# wearable_sch.net
KiCad netlist of a schematic drawn in Altium Designer
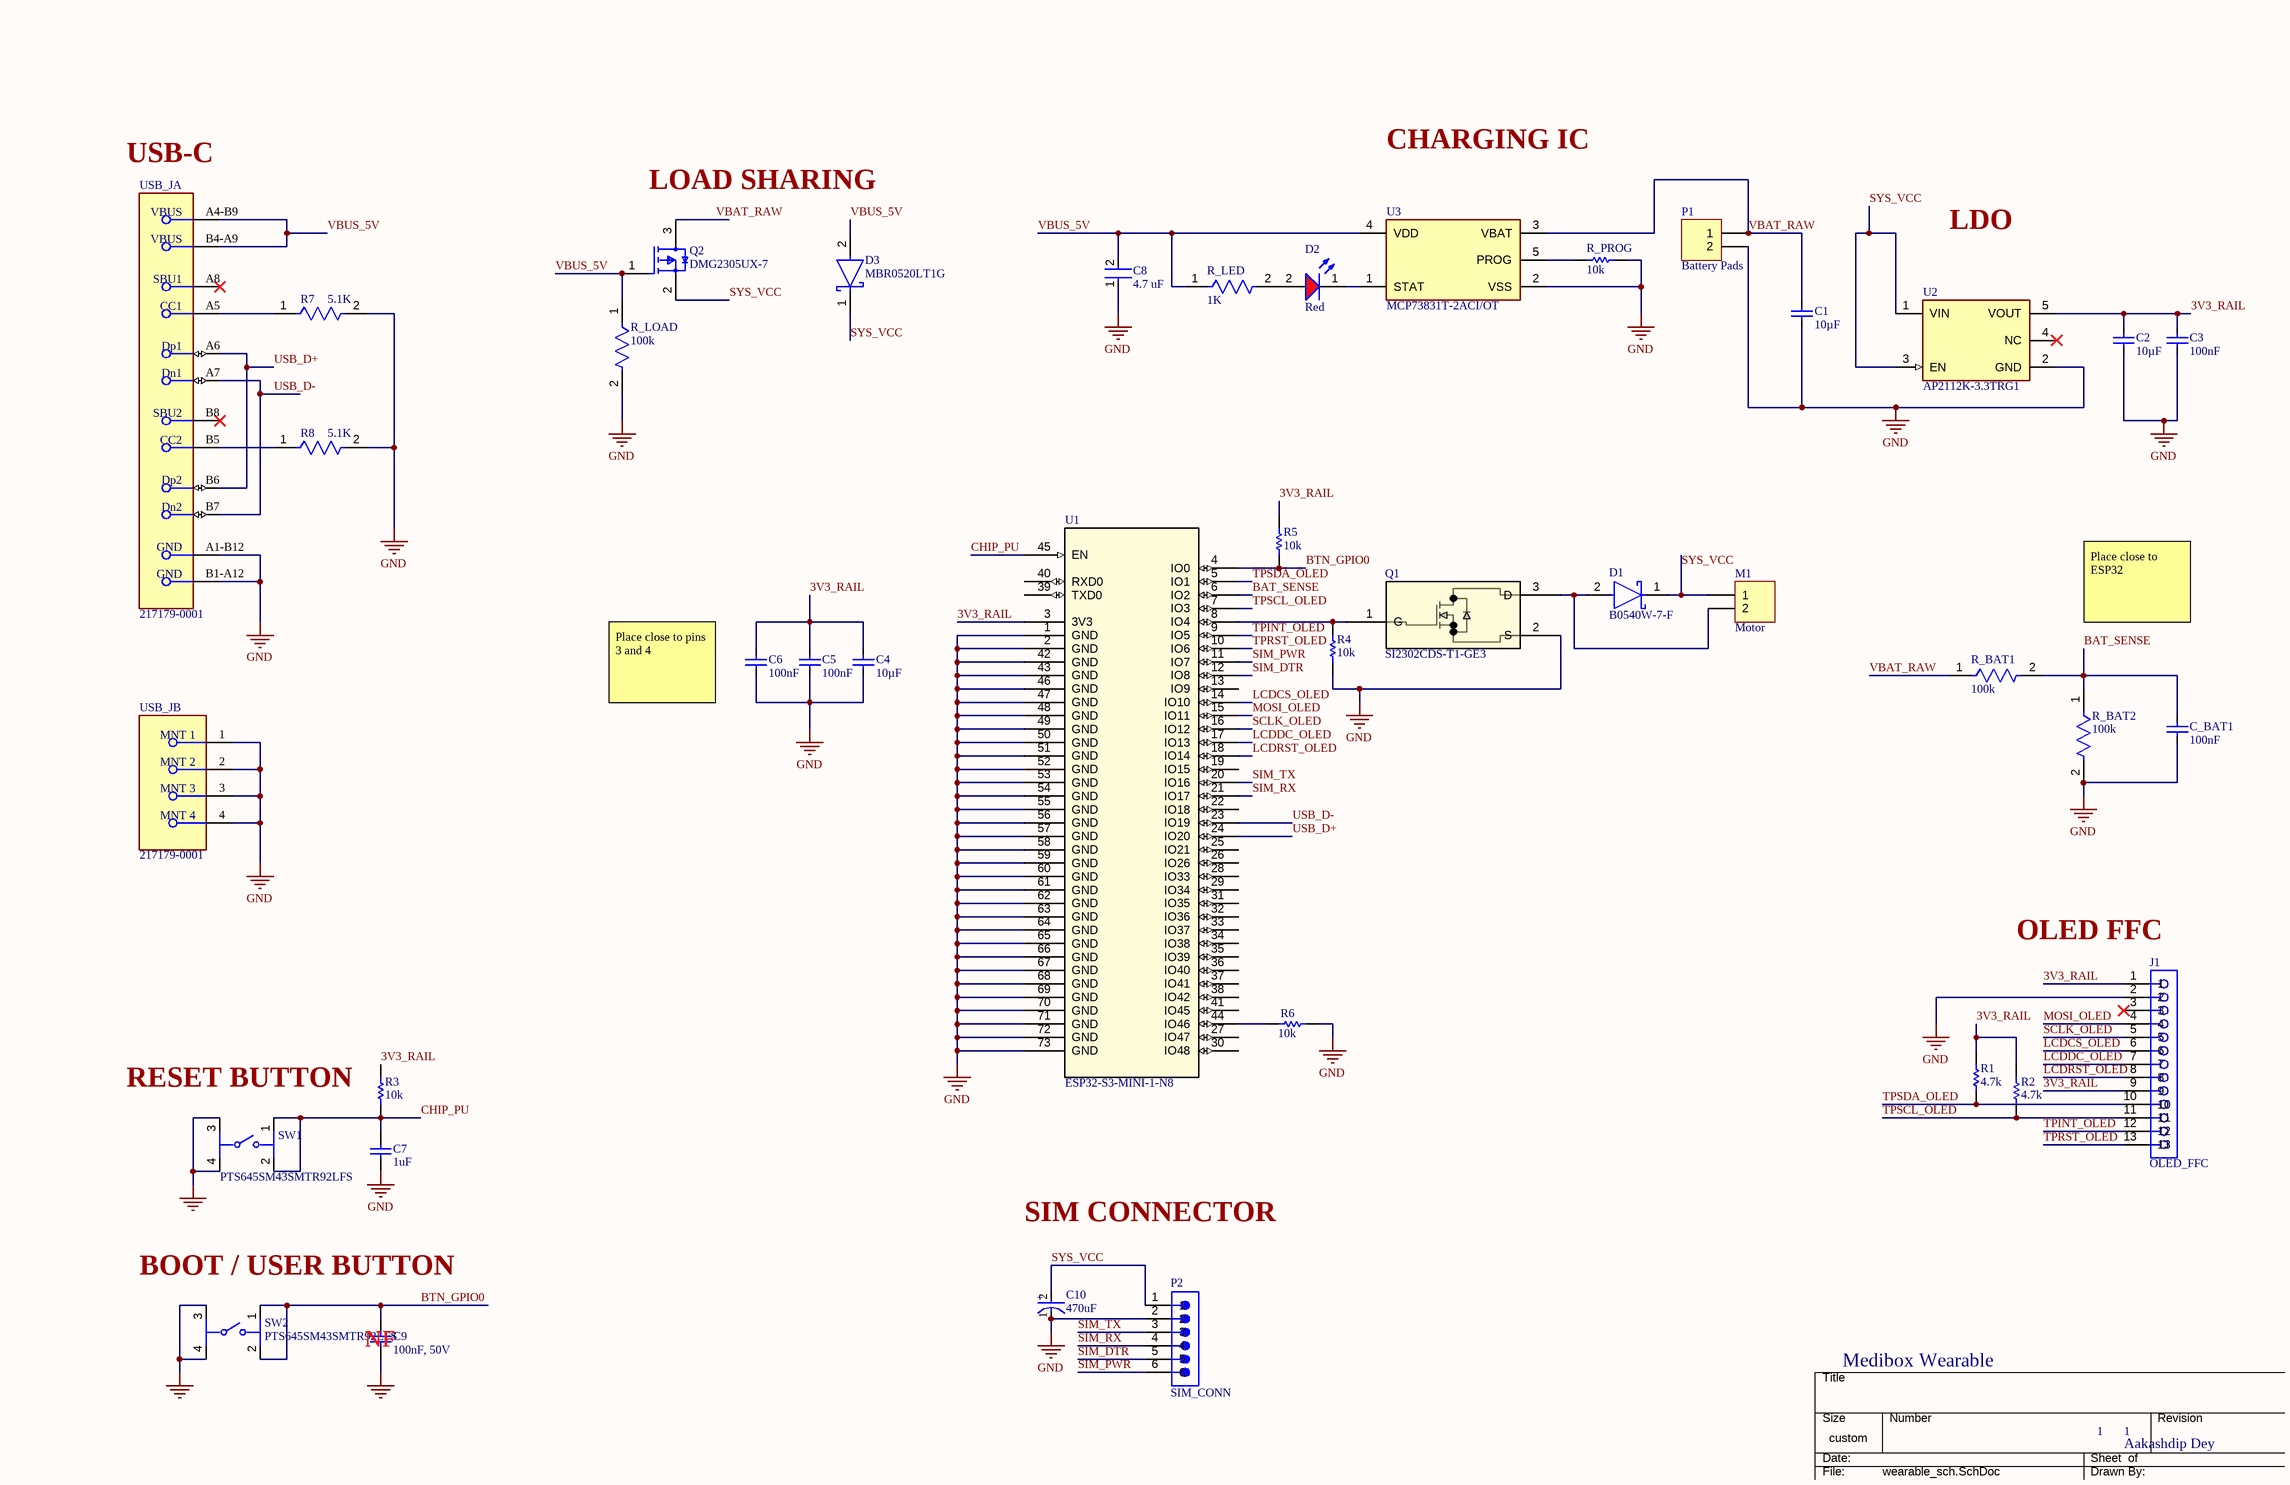
[diagram p0: wearable_sch.SchDoc]

(export (version "E")
  (design (tool "Eeschema 10.0.6"))
  (components
    (comp (ref "C1")
      (value "10µF")
      (footprint "CAPC2013X135X45ML10T25")
      (fields
        (field (name "TOLERANCE") "10%")
        (field (name "MANUFACTURER") "Murata")
        (field (name "MANUFACTURER PART NUMBER") "GRM21BR61E106KA73L")
      )
      (libsource (lib "WCT") (part "CAP_10uF_25V_0805"))
    )
    (comp (ref "C2")
      (value "10µF")
      (footprint "CAPC2013X135X45ML10T25")
      (fields
        (field (name "TOLERANCE") "10%")
        (field (name "MANUFACTURER") "Murata")
        (field (name "MANUFACTURER PART NUMBER") "GRM21BR61E106KA73L")
      )
      (libsource (lib "WCT") (part "CAP_10uF_25V_0805"))
    )
    (comp (ref "C3")
      (value "100nF")
      (footprint "0603C_L")
      (fields
        (field (name "MANUFACTURER") "Yageo")
        (field (name "MANUFACTURER PART NUMBER") "CC0603ZRY5V9BB104")
      )
      (libsource (lib "WCT") (part "Cap100nF_50V_0603"))
    )
    (comp (ref "C4")
      (value "10µF")
      (footprint "CAPC2013X135X45ML10T25")
      (fields
        (field (name "TOLERANCE") "10%")
        (field (name "MANUFACTURER") "Murata")
        (field (name "MANUFACTURER PART NUMBER") "GRM21BR61E106KA73L")
      )
      (libsource (lib "WCT") (part "CAP_10uF_25V_0805"))
    )
    (comp (ref "C5")
      (value "100nF")
      (footprint "0603C_L")
      (fields
        (field (name "MANUFACTURER") "Yageo")
        (field (name "MANUFACTURER PART NUMBER") "CC0603ZRY5V9BB104")
      )
      (libsource (lib "WCT") (part "Cap100nF_50V_0603"))
    )
    (comp (ref "C6")
      (value "100nF")
      (footprint "0603C_L")
      (fields
        (field (name "MANUFACTURER") "Yageo")
        (field (name "MANUFACTURER PART NUMBER") "CC0603ZRY5V9BB104")
      )
      (libsource (lib "WCT") (part "Cap100nF_50V_0603"))
    )
    (comp (ref "C7")
      (value "1uF")
      (footprint "CAPC2013X145X50LL20T25")
      (fields (field (name "MANUFACTURER") "Kemet") (field (name "PART NUMBER") "C0805C105K4PACTU"))
      (libsource (lib "Altium Content Vault") (part "CAP"))
    )
    (comp (ref "C8")
      (value "4.7 uF")
      (footprint "FP-GCM21B-0_15-IPC_A")
      (description "Ceramic Capacitor for Automotive 4.7uF ±20% 16VDC X7R 0805 Embossed T/R")
      (libsource (lib "Altium Content Vault") (part "02cd4be3c70576c341d710602a673aa"))
    )
    (comp (ref "C9")
      (value "100nF, 50V")
      (footprint "0603C_L")
      (description "CAP CER 0.1UF 50V X7R 0402")
      (fields
        (field (name "MANUFACTURER") "Samsung")
        (field (name "MANUFACTURER PART NUMBER") "CL05B104KB54PNC")
      )
      (libsource (lib "Schlib") (part "CL05B104KB54PNC"))
    )
    (comp (ref "C10")
      (value "470uF")
      (footprint "FP-ECAS-D4-MFG")
      (description "ECASD40E477M006KA0 Cap, 470UF, 2.5V, Alu Polymer, 2917 Rohs Compliant: Yes")
      (fields (field (name "TOLERANCE") "20%"))
      (libsource (lib "Altium Content Vault") (part "203bc49f2ac43e59fd269a8c329ed05"))
    )
    (comp (ref "C_BAT1")
      (value "100nF")
      (footprint "0603C_L")
      (fields
        (field (name "MANUFACTURER") "Yageo")
        (field (name "MANUFACTURER PART NUMBER") "CC0603ZRY5V9BB104")
      )
      (libsource (lib "WCT") (part "Cap100nF_50V_0603"))
    )
    (comp (ref "D1")
      (value "B0540W-7-F")
      (footprint "FP-SOD123-MFG")
      (description "DIODE SCHOTTKY 40V 500MA SOD123")
      (fields
        (field (name "MANUFACTURER") "Diodes Inc.")
        (field (name "OCTOPART") "https://octopart.com/b0540w-7-f-diodes+inc.-325656")
      )
      (libsource (lib "Altium Content Vault") (part "1d6ec82d83fb6aee721767c19dac4b9"))
    )
    (comp (ref "D2")
      (value "LED_Red0603")
      (footprint "0603_A")
      (description "Single Color LED, Red, Water Clear, 1.1mm")
      (fields
        (field (name "MANUFACTURER") "Wurth Electronics")
        (field (name "MANUFACTURER PART NUMBER") "150060RS75000")
        (field (name "COLOR") "Red")
      )
      (libsource (lib "WCT") (part "LED_Red0603"))
    )
    (comp (ref "D3")
      (value "MBR0520LT1G")
      (footprint "FP-425-04-IPC_C")
      (description "DIODE SCHOTTKY 20V 500MA SOD123")
      (libsource (lib "Altium Content Vault") (part "1d6ec82d83fb6aee721767c19dac4b9"))
    )
    (comp (ref "J1")
      (value "OLED_FFC")
      (footprint "MOLX-52806-1310")
      (fields (field (name "PARTNUMBER") "52806-1310") (field (name "MANUFACTURER") "Molex"))
      (libsource (lib "Altium Content Vault") (part "MOLX-52806-1310"))
    )
    (comp (ref "M1")
      (value "Motor")
      (footprint "HDR1X2")
      (description "Header, 2-Pin")
      (fields (field (name "PUBLISHER") "Altium Limited"))
      (libsource (lib "Miscellaneous Connectors") (part "Header 2"))
    )
    (comp (ref "P1")
      (value "Battery Pads")
      (footprint "HDR1X2")
      (description "Header, 2-Pin")
      (fields (field (name "PUBLISHER") "Altium Limited"))
      (libsource (lib "") (part "Header 2_1"))
    )
    (comp (ref "P2")
      (value "SIM_CONN")
      (footprint "SMTC-TSW-106-23-X-S")
      (description "0.025\" SQ Post Header, Through-hole, Vertical, -55 to 125 degC, 2.54 mm Pitch, 6-Pin, Male, RoHS")
      (fields (field (name "MANUFACTURER") "Samtec") (field (name "PARTNUMBER") "TSW-106-23-L-S"))
      (libsource (lib "Altium Content Vault") (part "SMTC-TSW-106-X-X-S-X"))
    )
    (comp (ref "Q1")
      (value "SI2302CDS-T1-GE3")
      (footprint "TO-236_VIS-L")
      (description "N-CHANNEL 20-V (D-S) MOSFET")
      (fields (field (name "COPYRIGHT") "Copyright (C) 2026 Ultra Librarian. All rights reserved."))
      (libsource (lib "wearable") (part "SI2302CDS-T1-GE3"))
    )
    (comp (ref "Q2")
      (value "DMG2305UX-7")
      (footprint "FP-SOT23-IPC_B")
      (description "MOSFET P-CH 20V 4.2A SOT23")
      (libsource (lib "Altium Content Vault") (part "87831b450059b469d4a68f5364f4496"))
    )
    (comp (ref "R1")
      (value "4.7k")
      (footprint "0603_L")
      (description "Res4K7_0603")
      (fields
        (field (name "MANUFACTURER") "Yageo")
        (field (name "TOLERANCE") "0.5%")
        (field (name "SOURCE") "WCT.SchLib")
      )
      (libsource (lib "WCT") (part "Res4K7_0603"))
    )
    (comp (ref "R2")
      (value "4.7k")
      (footprint "0603_L")
      (description "Res4K7_0603")
      (fields
        (field (name "MANUFACTURER") "Yageo")
        (field (name "TOLERANCE") "0.5%")
        (field (name "SOURCE") "WCT.SchLib")
      )
      (libsource (lib "WCT") (part "Res4K7_0603"))
    )
    (comp (ref "R3")
      (value "10k")
      (footprint "0603_L")
      (description "Res10K_0603")
      (fields
        (field (name "MANUFACTURER") "Panasonic Electronic Components")
        (field (name "MANUFACTURER PART NUMBER") "ERJ-3GEYJ102V")
        (field (name "SOURCE") "WCT.SchLib")
      )
      (libsource (lib "WCT") (part "Res10K_0603"))
    )
    (comp (ref "R4")
      (value "10k")
      (footprint "0603_L")
      (description "Res10K_0603")
      (fields
        (field (name "MANUFACTURER") "Panasonic Electronic Components")
        (field (name "MANUFACTURER PART NUMBER") "ERJ-3GEYJ102V")
        (field (name "SOURCE") "WCT.SchLib")
      )
      (libsource (lib "WCT") (part "Res10K_0603"))
    )
    (comp (ref "R5")
      (value "10k")
      (footprint "0603_L")
      (description "Res10K_0603")
      (fields
        (field (name "MANUFACTURER") "Panasonic Electronic Components")
        (field (name "MANUFACTURER PART NUMBER") "ERJ-3GEYJ102V")
        (field (name "SOURCE") "WCT.SchLib")
      )
      (libsource (lib "WCT") (part "Res10K_0603"))
    )
    (comp (ref "R6")
      (value "10k")
      (footprint "0603_L")
      (description "Res10K_0603")
      (fields
        (field (name "MANUFACTURER") "Panasonic Electronic Components")
        (field (name "MANUFACTURER PART NUMBER") "ERJ-3GEYJ102V")
        (field (name "SOURCE") "WCT.SchLib")
      )
      (libsource (lib "WCT") (part "Res10K_0603"))
    )
    (comp (ref "R7")
      (value "5.1K")
      (footprint "FP-CRCW0402-e3-IPC_A")
      (description "RES Thick Film, 5.1kΩ, 5%, 0.063W, 200ppm/°C, 0402")
      (fields (field (name "TOLERANCE") "5%"))
      (libsource (lib "Altium Content Vault") (part "1029c3af85768c4190bb7ad29bc67b5"))
    )
    (comp (ref "R8")
      (value "5.1K")
      (footprint "FP-CRCW0402-e3-IPC_A")
      (description "RES Thick Film, 5.1kΩ, 5%, 0.063W, 200ppm/°C, 0402")
      (fields (field (name "TOLERANCE") "5%"))
      (libsource (lib "Altium Content Vault") (part "1029c3af85768c4190bb7ad29bc67b5"))
    )
    (comp (ref "R_BAT1")
      (value "100k")
      (footprint "FP-MCS0402-MFG")
      (description "RES SMD 1.2K OHM 1% 1/10W 0402")
      (fields (field (name "TOLERANCE") "0.1%"))
      (libsource (lib "Altium Content Vault") (part "1029c3af85768c4190bb7ad29bc67b5"))
    )
    (comp (ref "R_BAT2")
      (value "100k")
      (footprint "FP-MCS0402-MFG")
      (description "RES SMD 1.2K OHM 1% 1/10W 0402")
      (fields (field (name "TOLERANCE") "0.1%"))
      (libsource (lib "Altium Content Vault") (part "1029c3af85768c4190bb7ad29bc67b5"))
    )
    (comp (ref "R_LED")
      (value "1K")
      (footprint "FP-AC0402-IPC_C")
      (description "RES 1kΩ ±1% 0.063W 0402")
      (libsource (lib "Altium Content Vault") (part "1029c3af85768c4190bb7ad29bc67b5"))
    )
    (comp (ref "R_LOAD")
      (value "100k")
      (footprint "FP-MCS0402-MFG")
      (description "RES SMD 1.2K OHM 1% 1/10W 0402")
      (fields (field (name "TOLERANCE") "0.1%"))
      (libsource (lib "Altium Content Vault") (part "1029c3af85768c4190bb7ad29bc67b5"))
    )
    (comp (ref "R_PROG")
      (value "10k")
      (footprint "0603_L")
      (description "Res10K_0603")
      (fields
        (field (name "MANUFACTURER") "Panasonic Electronic Components")
        (field (name "MANUFACTURER PART NUMBER") "ERJ-3GEYJ102V")
        (field (name "SOURCE") "WCT.SchLib")
      )
      (libsource (lib "WCT") (part "Res10K_0603"))
    )
    (comp (ref "SW1")
      (value "PTS645SM43SMTR92LFS")
      (footprint "FP-PTS645SM43SMTR92LFS-MFG")
      (description "SWITCH TACTILE SPST-NO 0.05A 12V")
      (libsource (lib "wearable") (part "CMP-2000-05160-2"))
    )
    (comp (ref "SW2")
      (value "PTS645SM43SMTR92LFS")
      (footprint "FP-PTS645SM43SMTR92LFS-MFG")
      (description "SWITCH TACTILE SPST-NO 0.05A 12V")
      (libsource (lib "wearable") (part "CMP-2000-05160-2"))
    )
    (comp (ref "U1")
      (value "ESP32-S3-MINI-1-N8")
      (footprint "ESP32-S3-MINI-1_EXP")
      (description "SMD module, ESP32-S3FN8, 8 MB SPI flash, PCB antenna")
      (fields (field (name "MANUFACTURER") "Espressif Systems") (field (name "LCSC PART NO.") "C2913206"))
      (libsource (lib "wearable") (part "ESP32-S3"))
    )
    (comp (ref "U2")
      (value "AP2112K-3.3TRG1")
      (footprint "FP-SOT25-IPC_A")
      (description "IC REG LINEAR 3.3V 600MA SOT25")
      (libsource (lib "Altium Content Vault") (part "c8ab751aee5229183125ab046a11caa"))
    )
    (comp (ref "U3")
      (value "MCP73831T-2ACI/OT")
      (footprint "FP-C04-091-OT-IPC_B")
      (description "IC CONTROLLR LI-ION 4.2V SOT23-5")
      (libsource (lib "Altium Content Vault") (part "61f5a3bb3429d9e0caadea342aa3b19"))
    )
    (comp (ref "USB_J")
      (value "217179-0001")
      (footprint "FP-2171790001-MFG")
      (description "CONN RCP USB2.0 TYP C 24P SMD RA")
      (libsource (lib "Altium Content Vault") (part "8b86497a633d14b3f74642136fc0ce6"))
    )
  )
  (nets
    (net (code "1") (name "/3V3_RAIL") (class "Default")
      (node (ref "C2") (pin "2") (pinfunction "2_2") (pintype "passive"))
      (node (ref "C3") (pin "2") (pinfunction "2_2") (pintype "passive"))
      (node (ref "C4") (pin "2") (pinfunction "2_2") (pintype "passive"))
      (node (ref "C5") (pin "2") (pinfunction "2_2") (pintype "passive"))
      (node (ref "C6") (pin "2") (pinfunction "2_2") (pintype "passive"))
      (node (ref "J1") (pin "1") (pinfunction "1_1") (pintype "passive"))
      (node (ref "J1") (pin "9") (pinfunction "9_9") (pintype "passive"))
      (node (ref "R1") (pin "2") (pinfunction "2_2") (pintype "passive"))
      (node (ref "R2") (pin "2") (pinfunction "2_2") (pintype "passive"))
      (node (ref "R3") (pin "1") (pinfunction "1_1") (pintype "passive"))
      (node (ref "R5") (pin "2") (pinfunction "2_2") (pintype "passive"))
      (node (ref "U1") (pin "3") (pinfunction "3V3_3") (pintype "power_in"))
      (node (ref "U2") (pin "5") (pinfunction "VOUT_5") (pintype "power_in"))
    )
    (net (code "2") (name "/BAT_SENSE") (class "Default")
      (node (ref "C_BAT1") (pin "2") (pinfunction "2_2") (pintype "passive"))
      (node (ref "R_BAT1") (pin "2") (pinfunction "2_2") (pintype "passive"))
      (node (ref "R_BAT2") (pin "1") (pinfunction "1_1") (pintype "passive"))
      (node (ref "U1") (pin "6") (pinfunction "IO2_6") (pintype "bidirectional"))
    )
    (net (code "3") (name "/BTN_GPIO0") (class "Default")
      (node (ref "C9") (pin "2") (pinfunction "2_2") (pintype "passive"))
      (node (ref "R5") (pin "1") (pinfunction "1_1") (pintype "passive"))
      (node (ref "SW2") (pin "1") (pinfunction "1_1") (pintype "passive"))
      (node (ref "SW2") (pin "2") (pinfunction "2_2") (pintype "passive"))
      (node (ref "U1") (pin "4") (pinfunction "IO0_4") (pintype "bidirectional"))
    )
    (net (code "4") (name "/CHIP_PU") (class "Default")
      (node (ref "C7") (pin "2") (pinfunction "2_2") (pintype "passive"))
      (node (ref "R3") (pin "2") (pinfunction "2_2") (pintype "passive"))
      (node (ref "SW1") (pin "1") (pinfunction "1_1") (pintype "passive"))
      (node (ref "SW1") (pin "2") (pinfunction "2_2") (pintype "passive"))
      (node (ref "U1") (pin "45") (pinfunction "EN_45") (pintype "input"))
    )
    (net (code "5") (name "/LCDCS_OLED") (class "Default")
      (node (ref "J1") (pin "6") (pinfunction "6_6") (pintype "passive"))
      (node (ref "U1") (pin "14") (pinfunction "IO10_14") (pintype "bidirectional"))
    )
    (net (code "6") (name "/LCDDC_OLED") (class "Default")
      (node (ref "J1") (pin "7") (pinfunction "7_7") (pintype "passive"))
      (node (ref "U1") (pin "17") (pinfunction "IO13_17") (pintype "bidirectional"))
    )
    (net (code "7") (name "/LCDRST_OLED") (class "Default")
      (node (ref "J1") (pin "8") (pinfunction "8_8") (pintype "passive"))
      (node (ref "U1") (pin "18") (pinfunction "IO14_18") (pintype "bidirectional"))
    )
    (net (code "8") (name "/MOSI_OLED") (class "Default")
      (node (ref "J1") (pin "4") (pinfunction "4_4") (pintype "passive"))
      (node (ref "U1") (pin "15") (pinfunction "IO11_15") (pintype "bidirectional"))
    )
    (net (code "9") (name "/SCLK_OLED") (class "Default")
      (node (ref "J1") (pin "5") (pinfunction "5_5") (pintype "passive"))
      (node (ref "U1") (pin "16") (pinfunction "IO12_16") (pintype "bidirectional"))
    )
    (net (code "10") (name "/SIM_DTR") (class "Default")
      (node (ref "P2") (pin "5") (pinfunction "5_5") (pintype "passive"))
      (node (ref "U1") (pin "12") (pinfunction "IO8_12") (pintype "bidirectional"))
    )
    (net (code "11") (name "/SIM_PWR") (class "Default")
      (node (ref "P2") (pin "6") (pinfunction "6_6") (pintype "passive"))
      (node (ref "U1") (pin "11") (pinfunction "IO7_11") (pintype "bidirectional"))
    )
    (net (code "12") (name "/SIM_RX") (class "Default")
      (node (ref "P2") (pin "4") (pinfunction "4_4") (pintype "passive"))
      (node (ref "U1") (pin "21") (pinfunction "IO17_21") (pintype "bidirectional"))
    )
    (net (code "13") (name "/SIM_TX") (class "Default")
      (node (ref "P2") (pin "3") (pinfunction "3_3") (pintype "passive"))
      (node (ref "U1") (pin "20") (pinfunction "IO16_20") (pintype "bidirectional"))
    )
    (net (code "14") (name "/SYS_VCC") (class "Default")
      (node (ref "C10") (pin "2") (pinfunction "A_2") (pintype "passive"))
      (node (ref "D1") (pin "1") (pinfunction "C_1") (pintype "passive"))
      (node (ref "D3") (pin "1") (pinfunction "C_1") (pintype "passive"))
      (node (ref "M1") (pin "1") (pinfunction "1_1") (pintype "passive"))
      (node (ref "P2") (pin "1") (pinfunction "1_1") (pintype "passive"))
      (node (ref "Q2") (pin "2") (pinfunction "SOURCE_2") (pintype "passive"))
      (node (ref "U2") (pin "1") (pinfunction "VIN_1") (pintype "power_in"))
      (node (ref "U2") (pin "3") (pinfunction "EN_3") (pintype "input"))
    )
    (net (code "15") (name "/TPINT_OLED") (class "Default")
      (node (ref "J1") (pin "12") (pinfunction "12_12") (pintype "passive"))
      (node (ref "U1") (pin "9") (pinfunction "IO5_9") (pintype "bidirectional"))
    )
    (net (code "16") (name "/TPRST_OLED") (class "Default")
      (node (ref "J1") (pin "13") (pinfunction "13_13") (pintype "passive"))
      (node (ref "U1") (pin "10") (pinfunction "IO6_10") (pintype "bidirectional"))
    )
    (net (code "17") (name "/TPSCL_OLED") (class "Default")
      (node (ref "J1") (pin "11") (pinfunction "11_11") (pintype "passive"))
      (node (ref "R2") (pin "1") (pinfunction "1_1") (pintype "passive"))
      (node (ref "U1") (pin "7") (pinfunction "IO3_7") (pintype "bidirectional"))
    )
    (net (code "18") (name "/TPSDA_OLED") (class "Default")
      (node (ref "J1") (pin "10") (pinfunction "10_10") (pintype "passive"))
      (node (ref "R1") (pin "1") (pinfunction "1_1") (pintype "passive"))
      (node (ref "U1") (pin "5") (pinfunction "IO1_5") (pintype "bidirectional"))
    )
    (net (code "19") (name "/USB_D+") (class "Default")
      (node (ref "U1") (pin "24") (pinfunction "IO20_24") (pintype "bidirectional"))
      (node (ref "USB_J") (pin "A6") (pinfunction "Dp1_A6") (pintype "bidirectional"))
      (node (ref "USB_J") (pin "B6") (pinfunction "Dp2_B6") (pintype "bidirectional"))
    )
    (net (code "20") (name "/USB_D-") (class "Default")
      (node (ref "U1") (pin "23") (pinfunction "IO19_23") (pintype "bidirectional"))
      (node (ref "USB_J") (pin "A7") (pinfunction "Dn1_A7") (pintype "bidirectional"))
      (node (ref "USB_J") (pin "B7") (pinfunction "Dn2_B7") (pintype "bidirectional"))
    )
    (net (code "21") (name "/VBAT_RAW") (class "Default")
      (node (ref "C1") (pin "1") (pinfunction "1_1") (pintype "passive"))
      (node (ref "P1") (pin "1") (pinfunction "1_1") (pintype "passive"))
      (node (ref "Q2") (pin "3") (pinfunction "DRAIN_3") (pintype "passive"))
      (node (ref "R_BAT1") (pin "1") (pinfunction "1_1") (pintype "passive"))
      (node (ref "U3") (pin "3") (pinfunction "VBAT_3") (pintype "power_in"))
    )
    (net (code "22") (name "/VBUS_5V") (class "Default")
      (node (ref "C8") (pin "2") (pinfunction "2_2") (pintype "passive"))
      (node (ref "D3") (pin "2") (pinfunction "A_2") (pintype "passive"))
      (node (ref "Q2") (pin "1") (pinfunction "GATE_1") (pintype "passive"))
      (node (ref "R_LED") (pin "1") (pinfunction "1_1") (pintype "passive"))
      (node (ref "R_LOAD") (pin "1") (pinfunction "1_1") (pintype "passive"))
      (node (ref "U3") (pin "4") (pinfunction "VDD_4") (pintype "power_in"))
      (node (ref "USB_J") (pin "A4-B9") (pinfunction "VBUS_A4-B9") (pintype "power_in"))
      (node (ref "USB_J") (pin "B4-A9") (pinfunction "VBUS_B4-A9") (pintype "power_in"))
    )
    (net (code "23") (name "GND") (class "Default")
      (node (ref "C1") (pin "2") (pinfunction "2_2") (pintype "passive"))
      (node (ref "C10") (pin "1") (pinfunction "C_1") (pintype "passive"))
      (node (ref "C2") (pin "1") (pinfunction "1_1") (pintype "passive"))
      (node (ref "C3") (pin "1") (pinfunction "1_1") (pintype "passive"))
      (node (ref "C4") (pin "1") (pinfunction "1_1") (pintype "passive"))
      (node (ref "C5") (pin "1") (pinfunction "1_1") (pintype "passive"))
      (node (ref "C6") (pin "1") (pinfunction "1_1") (pintype "passive"))
      (node (ref "C7") (pin "1") (pinfunction "1_1") (pintype "passive"))
      (node (ref "C8") (pin "1") (pinfunction "1_1") (pintype "passive"))
      (node (ref "C9") (pin "1") (pinfunction "1_1") (pintype "passive"))
      (node (ref "C_BAT1") (pin "1") (pinfunction "1_1") (pintype "passive"))
      (node (ref "J1") (pin "2") (pinfunction "2_2") (pintype "passive"))
      (node (ref "P1") (pin "2") (pinfunction "2_2") (pintype "passive"))
      (node (ref "P2") (pin "2") (pinfunction "2_2") (pintype "passive"))
      (node (ref "Q1") (pin "2") (pinfunction "S_2") (pintype "passive"))
      (node (ref "R4") (pin "1") (pinfunction "1_1") (pintype "passive"))
      (node (ref "R6") (pin "2") (pinfunction "2_2") (pintype "passive"))
      (node (ref "R7") (pin "2") (pinfunction "2_2") (pintype "passive"))
      (node (ref "R8") (pin "2") (pinfunction "2_2") (pintype "passive"))
      (node (ref "R_BAT2") (pin "2") (pinfunction "2_2") (pintype "passive"))
      (node (ref "R_LOAD") (pin "2") (pinfunction "2_2") (pintype "passive"))
      (node (ref "R_PROG") (pin "2") (pinfunction "2_2") (pintype "passive"))
      (node (ref "SW1") (pin "3") (pinfunction "3_3") (pintype "passive"))
      (node (ref "SW1") (pin "4") (pinfunction "4_4") (pintype "passive"))
      (node (ref "SW2") (pin "3") (pinfunction "3_3") (pintype "passive"))
      (node (ref "SW2") (pin "4") (pinfunction "4_4") (pintype "passive"))
      (node (ref "U1") (pin "1") (pinfunction "GND_1") (pintype "power_in"))
      (node (ref "U1") (pin "2") (pinfunction "GND_2") (pintype "power_in"))
      (node (ref "U1") (pin "42") (pinfunction "GND_42") (pintype "power_in"))
      (node (ref "U1") (pin "43") (pinfunction "GND_43") (pintype "power_in"))
      (node (ref "U1") (pin "46") (pinfunction "GND_46") (pintype "power_in"))
      (node (ref "U1") (pin "47") (pinfunction "GND_47") (pintype "power_in"))
      (node (ref "U1") (pin "48") (pinfunction "GND_48") (pintype "power_in"))
      (node (ref "U1") (pin "49") (pinfunction "GND_49") (pintype "power_in"))
      (node (ref "U1") (pin "50") (pinfunction "GND_50") (pintype "power_in"))
      (node (ref "U1") (pin "51") (pinfunction "GND_51") (pintype "power_in"))
      (node (ref "U1") (pin "52") (pinfunction "GND_52") (pintype "power_in"))
      (node (ref "U1") (pin "53") (pinfunction "GND_53") (pintype "power_in"))
      (node (ref "U1") (pin "54") (pinfunction "GND_54") (pintype "power_in"))
      (node (ref "U1") (pin "55") (pinfunction "GND_55") (pintype "power_in"))
      (node (ref "U1") (pin "56") (pinfunction "GND_56") (pintype "power_in"))
      (node (ref "U1") (pin "57") (pinfunction "GND_57") (pintype "power_in"))
      (node (ref "U1") (pin "58") (pinfunction "GND_58") (pintype "power_in"))
      (node (ref "U1") (pin "59") (pinfunction "GND_59") (pintype "power_in"))
      (node (ref "U1") (pin "60") (pinfunction "GND_60") (pintype "power_in"))
      (node (ref "U1") (pin "61") (pinfunction "GND_61") (pintype "power_in"))
      (node (ref "U1") (pin "62") (pinfunction "GND_62") (pintype "power_in"))
      (node (ref "U1") (pin "63") (pinfunction "GND_63") (pintype "power_in"))
      (node (ref "U1") (pin "64") (pinfunction "GND_64") (pintype "power_in"))
      (node (ref "U1") (pin "65") (pinfunction "GND_65") (pintype "power_in"))
      (node (ref "U1") (pin "66") (pinfunction "GND_66") (pintype "power_in"))
      (node (ref "U1") (pin "67") (pinfunction "GND_67") (pintype "power_in"))
      (node (ref "U1") (pin "68") (pinfunction "GND_68") (pintype "power_in"))
      (node (ref "U1") (pin "69") (pinfunction "GND_69") (pintype "power_in"))
      (node (ref "U1") (pin "70") (pinfunction "GND_70") (pintype "power_in"))
      (node (ref "U1") (pin "71") (pinfunction "GND_71") (pintype "power_in"))
      (node (ref "U1") (pin "72") (pinfunction "GND_72") (pintype "power_in"))
      (node (ref "U1") (pin "73") (pinfunction "GND_73") (pintype "power_in"))
      (node (ref "U2") (pin "2") (pinfunction "GND_2") (pintype "power_in"))
      (node (ref "U3") (pin "2") (pinfunction "VSS_2") (pintype "power_in"))
      (node (ref "USB_J") (pin "1") (pinfunction "MNT_1_1") (pintype "passive"))
      (node (ref "USB_J") (pin "2") (pinfunction "MNT_2_2") (pintype "passive"))
      (node (ref "USB_J") (pin "3") (pinfunction "MNT_3_3") (pintype "power_in"))
      (node (ref "USB_J") (pin "4") (pinfunction "MNT_4_4") (pintype "power_in"))
      (node (ref "USB_J") (pin "A1-B12") (pinfunction "GND_A1-B12") (pintype "power_in"))
      (node (ref "USB_J") (pin "B1-A12") (pinfunction "GND_B1-A12") (pintype "power_in"))
    )
    (net (code "24") (name "Net-(D1-A)") (class "Default")
      (node (ref "D1") (pin "2") (pinfunction "A_2") (pintype "passive"))
      (node (ref "M1") (pin "2") (pinfunction "2_2") (pintype "passive"))
      (node (ref "Q1") (pin "3") (pinfunction "D_3") (pintype "passive"))
    )
    (net (code "25") (name "Net-(D2-A)") (class "Default")
      (node (ref "D2") (pin "2") (pinfunction "A_2") (pintype "passive"))
      (node (ref "R_LED") (pin "2") (pinfunction "2_2") (pintype "passive"))
    )
    (net (code "26") (name "Net-(D2-K)") (class "Default")
      (node (ref "D2") (pin "1") (pinfunction "K_1") (pintype "passive"))
      (node (ref "U3") (pin "1") (pinfunction "STAT_1") (pintype "passive"))
    )
    (net (code "27") (name "Net-(Q1-G)") (class "Default")
      (node (ref "Q1") (pin "1") (pinfunction "G_1") (pintype "passive"))
      (node (ref "R4") (pin "2") (pinfunction "2_2") (pintype "passive"))
      (node (ref "U1") (pin "8") (pinfunction "IO4_8") (pintype "bidirectional"))
    )
    (net (code "28") (name "Net-(U1-IO46)") (class "Default")
      (node (ref "R6") (pin "1") (pinfunction "1_1") (pintype "passive"))
      (node (ref "U1") (pin "44") (pinfunction "IO46_44") (pintype "bidirectional"))
    )
    (net (code "29") (name "Net-(U3-PROG)") (class "Default")
      (node (ref "R_PROG") (pin "1") (pinfunction "1_1") (pintype "passive"))
      (node (ref "U3") (pin "5") (pinfunction "PROG_5") (pintype "passive"))
    )
    (net (code "30") (name "Net-(USB_JA-CC1)") (class "Default")
      (node (ref "R7") (pin "1") (pinfunction "1_1") (pintype "passive"))
      (node (ref "USB_J") (pin "A5") (pinfunction "CC1_A5") (pintype "passive"))
    )
    (net (code "31") (name "Net-(USB_JA-CC2)") (class "Default")
      (node (ref "R8") (pin "1") (pinfunction "1_1") (pintype "passive"))
      (node (ref "USB_J") (pin "B5") (pinfunction "CC2_B5") (pintype "passive"))
    )
    (net (code "32") (name "unconnected-(J1-Pad3)") (class "Default")
      (node (ref "J1") (pin "3") (pinfunction "3_3") (pintype "passive+no_connect"))
    )
    (net (code "33") (name "unconnected-(U1-IO9-Pad13)") (class "Default")
      (node (ref "U1") (pin "13") (pinfunction "IO9_13") (pintype "bidirectional"))
    )
    (net (code "34") (name "unconnected-(U1-IO15-Pad19)") (class "Default")
      (node (ref "U1") (pin "19") (pinfunction "IO15_19") (pintype "bidirectional"))
    )
    (net (code "35") (name "unconnected-(U1-IO18-Pad22)") (class "Default")
      (node (ref "U1") (pin "22") (pinfunction "IO18_22") (pintype "bidirectional"))
    )
    (net (code "36") (name "unconnected-(U1-IO21-Pad25)") (class "Default")
      (node (ref "U1") (pin "25") (pinfunction "IO21_25") (pintype "bidirectional"))
    )
    (net (code "37") (name "unconnected-(U1-IO26-Pad26)") (class "Default")
      (node (ref "U1") (pin "26") (pinfunction "IO26_26") (pintype "bidirectional"))
    )
    (net (code "38") (name "unconnected-(U1-IO33-Pad28)") (class "Default")
      (node (ref "U1") (pin "28") (pinfunction "IO33_28") (pintype "bidirectional"))
    )
    (net (code "39") (name "unconnected-(U1-IO34-Pad29)") (class "Default")
      (node (ref "U1") (pin "29") (pinfunction "IO34_29") (pintype "bidirectional"))
    )
    (net (code "40") (name "unconnected-(U1-IO35-Pad31)") (class "Default")
      (node (ref "U1") (pin "31") (pinfunction "IO35_31") (pintype "bidirectional"))
    )
    (net (code "41") (name "unconnected-(U1-IO36-Pad32)") (class "Default")
      (node (ref "U1") (pin "32") (pinfunction "IO36_32") (pintype "bidirectional"))
    )
    (net (code "42") (name "unconnected-(U1-IO37-Pad33)") (class "Default")
      (node (ref "U1") (pin "33") (pinfunction "IO37_33") (pintype "bidirectional"))
    )
    (net (code "43") (name "unconnected-(U1-IO38-Pad34)") (class "Default")
      (node (ref "U1") (pin "34") (pinfunction "IO38_34") (pintype "bidirectional"))
    )
    (net (code "44") (name "unconnected-(U1-IO39-Pad35)") (class "Default")
      (node (ref "U1") (pin "35") (pinfunction "IO39_35") (pintype "bidirectional"))
    )
    (net (code "45") (name "unconnected-(U1-IO40-Pad36)") (class "Default")
      (node (ref "U1") (pin "36") (pinfunction "IO40_36") (pintype "bidirectional"))
    )
    (net (code "46") (name "unconnected-(U1-IO41-Pad37)") (class "Default")
      (node (ref "U1") (pin "37") (pinfunction "IO41_37") (pintype "bidirectional"))
    )
    (net (code "47") (name "unconnected-(U1-IO42-Pad38)") (class "Default")
      (node (ref "U1") (pin "38") (pinfunction "IO42_38") (pintype "bidirectional"))
    )
    (net (code "48") (name "unconnected-(U1-IO45-Pad41)") (class "Default")
      (node (ref "U1") (pin "41") (pinfunction "IO45_41") (pintype "bidirectional"))
    )
    (net (code "49") (name "unconnected-(U1-IO47-Pad27)") (class "Default")
      (node (ref "U1") (pin "27") (pinfunction "IO47_27") (pintype "bidirectional"))
    )
    (net (code "50") (name "unconnected-(U1-IO48-Pad30)") (class "Default")
      (node (ref "U1") (pin "30") (pinfunction "IO48_30") (pintype "bidirectional"))
    )
    (net (code "51") (name "unconnected-(U1-RXD0-Pad40)") (class "Default")
      (node (ref "U1") (pin "40") (pinfunction "RXD0_40") (pintype "bidirectional"))
    )
    (net (code "52") (name "unconnected-(U1-TXD0-Pad39)") (class "Default")
      (node (ref "U1") (pin "39") (pinfunction "TXD0_39") (pintype "bidirectional"))
    )
    (net (code "53") (name "unconnected-(U2-NC-Pad4)") (class "Default")
      (node (ref "U2") (pin "4") (pinfunction "NC_4") (pintype "passive+no_connect"))
    )
    (net (code "54") (name "unconnected-(USB_JA-SBU1-PadA8)") (class "Default")
      (node (ref "USB_J") (pin "A8") (pinfunction "SBU1_A8") (pintype "passive+no_connect"))
    )
    (net (code "55") (name "unconnected-(USB_JA-SBU2-PadB8)") (class "Default")
      (node (ref "USB_J") (pin "B8") (pinfunction "SBU2_B8") (pintype "passive+no_connect"))
    )
  )
)
